# SNI_PROTO_sch.net
KiCad netlist of a schematic drawn in Altium Designer
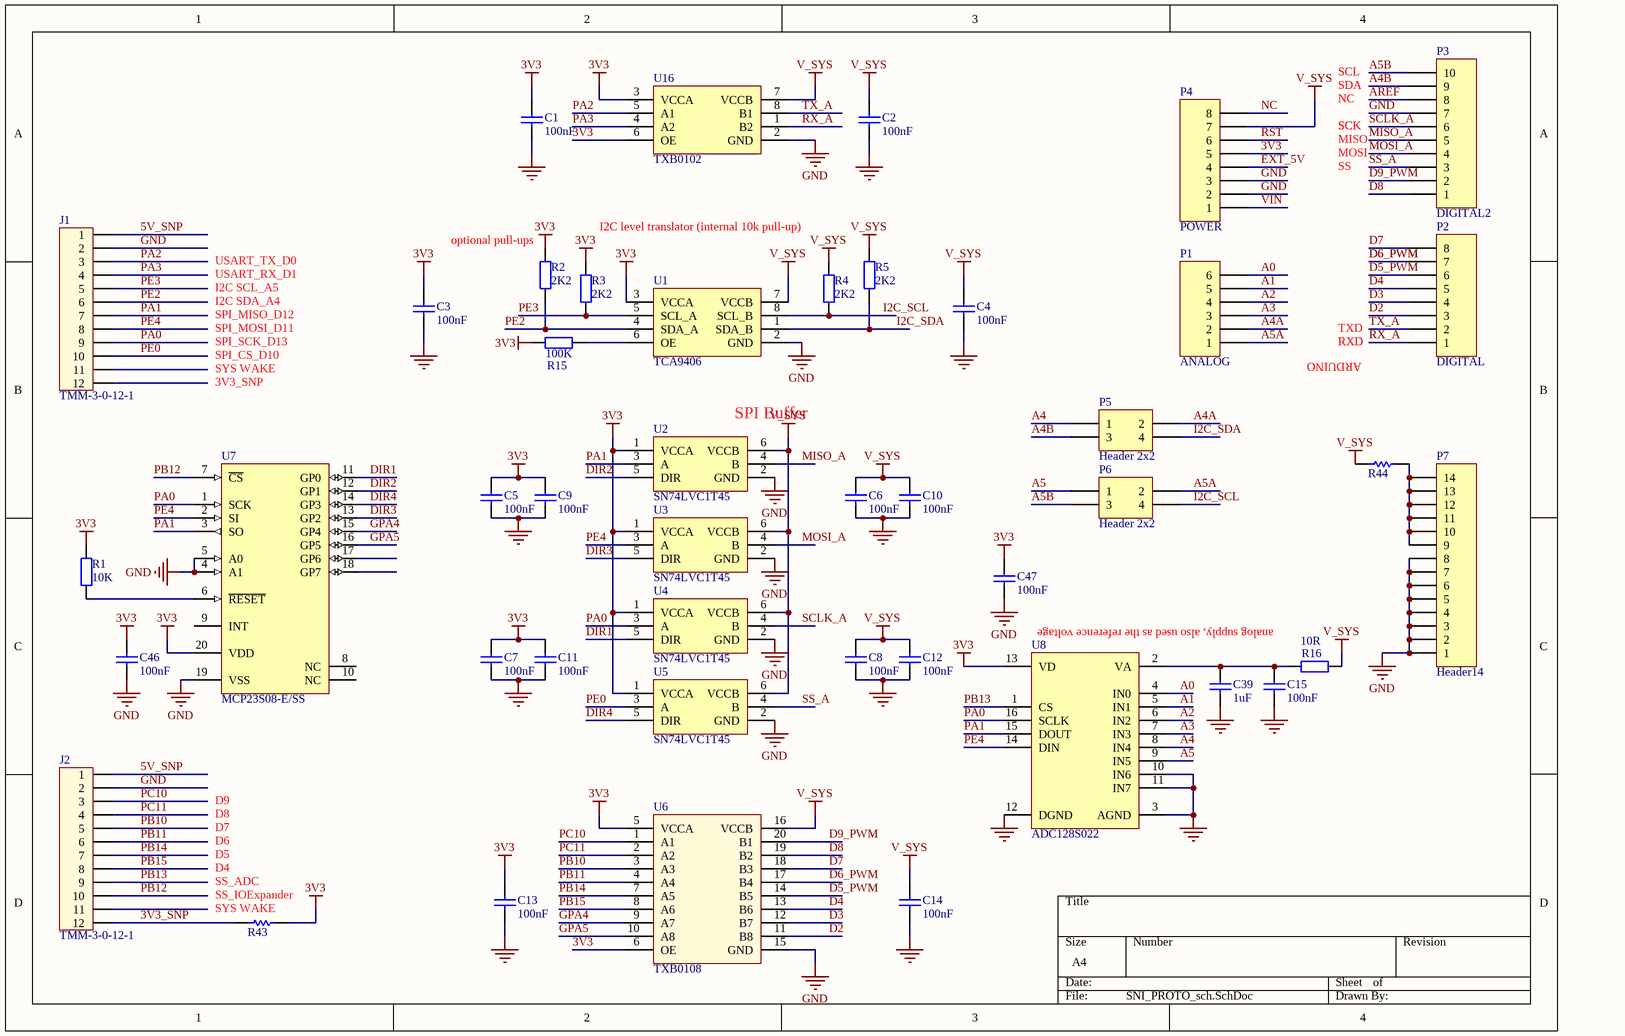
[diagram p0: SNI_PROTO_sch.SchDoc]

(export (version "E")
  (design (tool "Eeschema 10.0.6"))
  (components
    (comp (ref "C1")
      (value "100nF")
      (footprint "CAPC0402(1005)60_L")
      (description "CAP 100nF 10V ±5% 0402 (1005 Metric) Thickness 0.6mm SMD")
      (fields (field (name "TOLERANCE") "Â±5%") (field (name "Comment") "CAP 100nF 10V 0402(1005)"))
      (libsource (lib "Altium Content Vault") (part "CMP-1034-02064-1"))
    )
    (comp (ref "C2")
      (value "100nF")
      (footprint "CAPC0402(1005)60_L")
      (description "CAP 100nF 10V ±5% 0402 (1005 Metric) Thickness 0.6mm SMD")
      (fields (field (name "TOLERANCE") "Â±5%") (field (name "Comment") "CAP 100nF 10V 0402(1005)"))
      (libsource (lib "Altium Content Vault") (part "CMP-1034-02064-1"))
    )
    (comp (ref "C3")
      (value "100nF")
      (footprint "CAPC0402(1005)60_L")
      (description "CAP 100nF 10V ±5% 0402 (1005 Metric) Thickness 0.6mm SMD")
      (fields (field (name "TOLERANCE") "Â±5%") (field (name "Comment") "CAP 100nF 10V 0402(1005)"))
      (libsource (lib "Altium Content Vault") (part "CMP-1034-02064-1"))
    )
    (comp (ref "C4")
      (value "100nF")
      (footprint "CAPC0402(1005)60_L")
      (description "CAP 100nF 10V ±5% 0402 (1005 Metric) Thickness 0.6mm SMD")
      (fields (field (name "TOLERANCE") "Â±5%") (field (name "Comment") "CAP 100nF 10V 0402(1005)"))
      (libsource (lib "Altium Content Vault") (part "CMP-1034-02064-1"))
    )
    (comp (ref "C5")
      (value "100nF")
      (footprint "CAPC0402(1005)60_L")
      (description "CAP 100nF 10V ±5% 0402 (1005 Metric) Thickness 0.6mm SMD")
      (fields (field (name "TOLERANCE") "Â±5%") (field (name "Comment") "CAP 100nF 10V 0402(1005)"))
      (libsource (lib "Altium Content Vault") (part "CMP-1034-02064-1"))
    )
    (comp (ref "C6")
      (value "100nF")
      (footprint "CAPC0402(1005)60_L")
      (description "CAP 100nF 10V ±5% 0402 (1005 Metric) Thickness 0.6mm SMD")
      (fields (field (name "TOLERANCE") "Â±5%") (field (name "Comment") "CAP 100nF 10V 0402(1005)"))
      (libsource (lib "Altium Content Vault") (part "CMP-1034-02064-1"))
    )
    (comp (ref "C7")
      (value "100nF")
      (footprint "CAPC0402(1005)60_L")
      (description "CAP 100nF 10V ±5% 0402 (1005 Metric) Thickness 0.6mm SMD")
      (fields (field (name "TOLERANCE") "Â±5%") (field (name "Comment") "CAP 100nF 10V 0402(1005)"))
      (libsource (lib "Altium Content Vault") (part "CMP-1034-02064-1"))
    )
    (comp (ref "C8")
      (value "100nF")
      (footprint "CAPC0402(1005)60_L")
      (description "CAP 100nF 10V ±5% 0402 (1005 Metric) Thickness 0.6mm SMD")
      (fields (field (name "TOLERANCE") "Â±5%") (field (name "Comment") "CAP 100nF 10V 0402(1005)"))
      (libsource (lib "Altium Content Vault") (part "CMP-1034-02064-1"))
    )
    (comp (ref "C9")
      (value "100nF")
      (footprint "CAPC0402(1005)60_L")
      (description "CAP 100nF 10V ±5% 0402 (1005 Metric) Thickness 0.6mm SMD")
      (fields (field (name "TOLERANCE") "Â±5%") (field (name "Comment") "CAP 100nF 10V 0402(1005)"))
      (libsource (lib "Altium Content Vault") (part "CMP-1034-02064-1"))
    )
    (comp (ref "C10")
      (value "100nF")
      (footprint "CAPC0402(1005)60_L")
      (description "CAP 100nF 10V ±5% 0402 (1005 Metric) Thickness 0.6mm SMD")
      (fields (field (name "TOLERANCE") "Â±5%") (field (name "Comment") "CAP 100nF 10V 0402(1005)"))
      (libsource (lib "Altium Content Vault") (part "CMP-1034-02064-1"))
    )
    (comp (ref "C11")
      (value "100nF")
      (footprint "CAPC0402(1005)60_L")
      (description "CAP 100nF 10V ±5% 0402 (1005 Metric) Thickness 0.6mm SMD")
      (fields (field (name "TOLERANCE") "Â±5%") (field (name "Comment") "CAP 100nF 10V 0402(1005)"))
      (libsource (lib "Altium Content Vault") (part "CMP-1034-02064-1"))
    )
    (comp (ref "C12")
      (value "100nF")
      (footprint "CAPC0402(1005)60_L")
      (description "CAP 100nF 10V ±5% 0402 (1005 Metric) Thickness 0.6mm SMD")
      (fields (field (name "TOLERANCE") "Â±5%") (field (name "Comment") "CAP 100nF 10V 0402(1005)"))
      (libsource (lib "Altium Content Vault") (part "CMP-1034-02064-1"))
    )
    (comp (ref "C13")
      (value "100nF")
      (footprint "CAPC0402(1005)60_L")
      (description "CAP 100nF 10V ±5% 0402 (1005 Metric) Thickness 0.6mm SMD")
      (fields (field (name "TOLERANCE") "Â±5%") (field (name "Comment") "CAP 100nF 10V 0402(1005)"))
      (libsource (lib "Altium Content Vault") (part "CMP-1034-02064-1"))
    )
    (comp (ref "C14")
      (value "100nF")
      (footprint "CAPC0402(1005)60_L")
      (description "CAP 100nF 10V ±5% 0402 (1005 Metric) Thickness 0.6mm SMD")
      (fields (field (name "TOLERANCE") "Â±5%") (field (name "Comment") "CAP 100nF 10V 0402(1005)"))
      (libsource (lib "Altium Content Vault") (part "CMP-1034-02064-1"))
    )
    (comp (ref "C15")
      (value "100nF")
      (footprint "CAPC0402(1005)60_L")
      (description "CAP 100nF 10V ±5% 0402 (1005 Metric) Thickness 0.6mm SMD")
      (fields (field (name "TOLERANCE") "Â±5%") (field (name "Comment") "CAP 100nF 10V 0402(1005)"))
      (libsource (lib "Altium Content Vault") (part "CMP-1034-02064-1"))
    )
    (comp (ref "C39")
      (value "1uF")
      (footprint "CAPC0402(1005)60_L")
      (description "CAP 1uF 10V ±20% 0402 (1005 Metric) Thickness 0.6mm SMD")
      (fields (field (name "TOLERANCE") "Â±20%") (field (name "Comment") "CAP 1uF 10V 0402(1005)"))
      (libsource (lib "Altium Content Vault") (part "CMP-1034-02117-1"))
    )
    (comp (ref "C46")
      (value "100nF")
      (footprint "CAPC0402(1005)60_L")
      (description "CAP 100nF 10V ±5% 0402 (1005 Metric) Thickness 0.6mm SMD")
      (fields (field (name "TOLERANCE") "Â±5%") (field (name "Comment") "CAP 100nF 10V 0402(1005)"))
      (libsource (lib "Altium Content Vault") (part "CMP-1034-02064-1"))
    )
    (comp (ref "C47")
      (value "100nF")
      (footprint "CAPC0402(1005)60_L")
      (description "CAP 100nF 10V ±5% 0402 (1005 Metric) Thickness 0.6mm SMD")
      (fields (field (name "TOLERANCE") "Â±5%") (field (name "Comment") "CAP 100nF 10V 0402(1005)"))
      (libsource (lib "Altium Content Vault") (part "CMP-1034-02064-1"))
    )
    (comp (ref "J1")
      (value "TMM-3-0-12-1")
      (footprint "TMM-3-0-12-1")
      (description "PLUG, DIP, 1.27MM, 12WAY")
      (fields (field (name "MANUFACTURER") "AMPHENOL"))
      (libsource (lib "TMM-3-0-12-1") (part "TMM-3-0-12-1"))
    )
    (comp (ref "J2")
      (value "TMM-3-0-12-1")
      (footprint "TMM-3-0-12-1")
      (description "PLUG, DIP, 1.27MM, 12WAY")
      (fields (field (name "MANUFACTURER") "AMPHENOL"))
      (libsource (lib "TMM-3-0-12-1") (part "TMM-3-0-12-1"))
    )
    (comp (ref "P1") (value "ANALOG") (footprint "H6A") (libsource (lib "Headers_various") (part "header6A")))
    (comp (ref "P2") (value "DIGITAL") (footprint "H8A") (libsource (lib "") (part "Header8A_1")))
    (comp (ref "P3")
      (value "DIGITAL2")
      (footprint "H10A")
      (libsource (lib "Headers_various") (part "Header10A"))
    )
    (comp (ref "P4") (value "POWER") (footprint "H8A") (libsource (lib "Headers_various") (part "Header8A")))
    (comp (ref "P5")
      (value "Header 2x2")
      (footprint "H2x2")
      (libsource (lib "Headers_various") (part "Header"))
    )
    (comp (ref "P6")
      (value "Header 2x2")
      (footprint "H2x2")
      (libsource (lib "Headers_various") (part "Header"))
    )
    (comp (ref "P7")
      (value "Header14")
      (footprint "H14")
      (libsource (lib "Headers_various") (part "Header14"))
    )
    (comp (ref "R1")
      (value "10K")
      (footprint "RESC0402(1005)_L")
      (description "10K 0.063W 1% 0402 (1005 Metric)  SMD")
      (fields (field (name "POWER") "0.063W") (field (name "TOLERANCE") "1%"))
      (libsource (lib "RES0402(1005)") (part "10K 0402(1005)_1"))
    )
    (comp (ref "R2")
      (value "2K2")
      (footprint "RESC0402(1005)_L")
      (description "2K2 0.063W 1% 0402 (1005 Metric)  SMD")
      (fields (field (name "POWER") "0.063W") (field (name "TOLERANCE") "1%"))
      (libsource (lib "RES0402(1005)") (part "2K2 0402(1005)"))
    )
    (comp (ref "R3")
      (value "2K2")
      (footprint "RESC0402(1005)_L")
      (description "2K2 0.063W 1% 0402 (1005 Metric)  SMD")
      (fields (field (name "POWER") "0.063W") (field (name "TOLERANCE") "1%"))
      (libsource (lib "RES0402(1005)") (part "2K2 0402(1005)"))
    )
    (comp (ref "R4")
      (value "2K2")
      (footprint "RESC0402(1005)_L")
      (description "2K2 0.063W 1% 0402 (1005 Metric)  SMD")
      (fields (field (name "POWER") "0.063W") (field (name "TOLERANCE") "1%"))
      (libsource (lib "RES0402(1005)") (part "2K2 0402(1005)"))
    )
    (comp (ref "R5")
      (value "2K2")
      (footprint "RESC0402(1005)_L")
      (description "2K2 0.063W 1% 0402 (1005 Metric)  SMD")
      (fields (field (name "POWER") "0.063W") (field (name "TOLERANCE") "1%"))
      (libsource (lib "RES0402(1005)") (part "2K2 0402(1005)"))
    )
    (comp (ref "R15")
      (value "100K")
      (footprint "RESC0402(1005)_L")
      (description "100K 0.063W 1% 0402 (1005 Metric)  SMD")
      (fields (field (name "POWER") "0.063W") (field (name "TOLERANCE") "1%"))
      (libsource (lib "RES0402(1005)") (part "100K 0402(1005)"))
    )
    (comp (ref "R16")
      (value "10R")
      (footprint "RESC0603(1608)_N")
      (description "10R 0.1W 1% 0603 (1608 Metric)  SMD")
      (fields (field (name "POWER") "0.1W") (field (name "TOLERANCE") "1%"))
      (libsource (lib "RES0603(1608)") (part "10R 0603(1608)"))
    )
    (comp (ref "R43")
      (value "Jumper 0805(2012)")
      (footprint "RESC0805(2012)_N")
      (description "Jumper 0805 (2012 Metric)")
      (fields (field (name "TOLERANCE") "None"))
      (libsource (lib "Altium Content Vault") (part "CMP-1013-00001-1"))
    )
    (comp (ref "R44")
      (value "1R 5% 1210(3225)")
      (footprint "RESC1210(3225)_N")
      (description "1R 0.5W 5% 1210 (3225 Metric)  SMD")
      (fields (field (name "POWER") "0.5 W") (field (name "TOLERANCE") "5 %"))
      (libsource (lib "Altium Content Vault") (part "CMP-1015-00002-1"))
    )
    (comp (ref "U1") (value "TCA9406") (footprint "LSSOP-8") (libsource (lib "TCA9406") (part "TCA9406")))
    (comp (ref "U2")
      (value "SN74LVC1T45")
      (footprint "SOT6_DRL")
      (libsource (lib "SN74LVC1T45") (part "SN74LVC1T45"))
    )
    (comp (ref "U3")
      (value "SN74LVC1T45")
      (footprint "SOT6_DRL")
      (libsource (lib "SN74LVC1T45") (part "SN74LVC1T45"))
    )
    (comp (ref "U4")
      (value "SN74LVC1T45")
      (footprint "SOT6_DRL")
      (libsource (lib "SN74LVC1T45") (part "SN74LVC1T45"))
    )
    (comp (ref "U5")
      (value "SN74LVC1T45")
      (footprint "SOT6_DRL")
      (libsource (lib "SN74LVC1T45") (part "SN74LVC1T45"))
    )
    (comp (ref "U6")
      (value "TXB0108")
      (footprint "UFDFN-20")
      (description "Translator, Bidirectional, 8 bits data rate 100Mbps")
      (fields
        (field (name "MANUFACTURER PART NUMBER") "TXB0108DQSR")
        (field (name "MANUFACTURER") "Texas Instruments")
      )
      (libsource (lib "TXB0108") (part "TXB0108"))
    )
    (comp (ref "U7")
      (value "MCP23S08-E/SS")
      (footprint "SSOP-SS20_N")
      (description "8-Bit I/O Expander with Serial Interface, 20-Pin SSOP, Extended Temperature")
      (fields (field (name "PUBLISHER") "Altium Limited"))
      (libsource (lib "Microchip Interface") (part "MCP23S08-E/SS"))
    )
    (comp (ref "U8")
      (value "ADC128S022")
      (footprint "TSSOP16")
      (libsource (lib "ADC128S022") (part "ADC128S022"))
    )
    (comp (ref "U16") (value "TXB0102") (footprint "VSSOP8") (libsource (lib "TXB0102") (part "TXB0102")))
  )
  (nets
    (net (code "1") (name "/3V3_SNP") (class "Default")
      (node (ref "J2") (pin "12") (pinfunction "12_12") (pintype "passive"))
      (node (ref "R43") (pin "1") (pinfunction "1_1") (pintype "passive"))
    )
    (net (code "2") (name "/5V_SNP") (class "Default")
      (node (ref "J1") (pin "1") (pinfunction "1_1") (pintype "passive"))
      (node (ref "J2") (pin "1") (pinfunction "1_1") (pintype "passive"))
    )
    (net (code "3") (name "/A0") (class "Default")
      (node (ref "P1") (pin "6") (pinfunction "6_6") (pintype "passive"))
      (node (ref "U8") (pin "4") (pinfunction "IN0_4") (pintype "passive"))
    )
    (net (code "4") (name "/A1") (class "Default")
      (node (ref "P1") (pin "5") (pinfunction "5_5") (pintype "passive"))
      (node (ref "U8") (pin "5") (pinfunction "IN1_5") (pintype "passive"))
    )
    (net (code "5") (name "/A2") (class "Default")
      (node (ref "P1") (pin "4") (pinfunction "4_4") (pintype "passive"))
      (node (ref "U8") (pin "6") (pinfunction "IN2_6") (pintype "passive"))
    )
    (net (code "6") (name "/A3") (class "Default")
      (node (ref "P1") (pin "3") (pinfunction "3_3") (pintype "passive"))
      (node (ref "U8") (pin "7") (pinfunction "IN3_7") (pintype "passive"))
    )
    (net (code "7") (name "/A4") (class "Default")
      (node (ref "P5") (pin "1") (pinfunction "1_1") (pintype "passive"))
      (node (ref "U8") (pin "8") (pinfunction "IN4_8") (pintype "passive"))
    )
    (net (code "8") (name "/A4A") (class "Default")
      (node (ref "P1") (pin "2") (pinfunction "2_2") (pintype "passive"))
      (node (ref "P5") (pin "2") (pinfunction "2_2") (pintype "passive"))
    )
    (net (code "9") (name "/A4B") (class "Default")
      (node (ref "P3") (pin "9") (pinfunction "9_9") (pintype "passive"))
      (node (ref "P5") (pin "3") (pinfunction "3_3") (pintype "passive"))
    )
    (net (code "10") (name "/A5") (class "Default")
      (node (ref "P6") (pin "1") (pinfunction "1_1") (pintype "passive"))
      (node (ref "U8") (pin "9") (pinfunction "IN5_9") (pintype "passive"))
    )
    (net (code "11") (name "/A5A") (class "Default")
      (node (ref "P1") (pin "1") (pinfunction "1_1") (pintype "passive"))
      (node (ref "P6") (pin "2") (pinfunction "2_2") (pintype "passive"))
    )
    (net (code "12") (name "/A5B") (class "Default")
      (node (ref "P3") (pin "10") (pinfunction "10_10") (pintype "passive"))
      (node (ref "P6") (pin "3") (pinfunction "3_3") (pintype "passive"))
    )
    (net (code "13") (name "/AREF") (class "Default")
      (node (ref "P3") (pin "8") (pinfunction "8_8") (pintype "passive"))
    )
    (net (code "14") (name "/D2") (class "Default")
      (node (ref "P2") (pin "3") (pinfunction "3_3") (pintype "passive"))
      (node (ref "U6") (pin "11") (pinfunction "B8_11") (pintype "passive"))
    )
    (net (code "15") (name "/D3") (class "Default")
      (node (ref "P2") (pin "4") (pinfunction "4_4") (pintype "passive"))
      (node (ref "U6") (pin "12") (pinfunction "B7_12") (pintype "passive"))
    )
    (net (code "16") (name "/D4") (class "Default")
      (node (ref "P2") (pin "5") (pinfunction "5_5") (pintype "passive"))
      (node (ref "U6") (pin "13") (pinfunction "B6_13") (pintype "passive"))
    )
    (net (code "17") (name "/D5_PWM") (class "Default")
      (node (ref "P2") (pin "6") (pinfunction "6_6") (pintype "passive"))
      (node (ref "U6") (pin "14") (pinfunction "B5_14") (pintype "passive"))
    )
    (net (code "18") (name "/D6_PWM") (class "Default")
      (node (ref "P2") (pin "7") (pinfunction "7_7") (pintype "passive"))
      (node (ref "U6") (pin "17") (pinfunction "B4_17") (pintype "passive"))
    )
    (net (code "19") (name "/D7") (class "Default")
      (node (ref "P2") (pin "8") (pinfunction "8_8") (pintype "passive"))
      (node (ref "U6") (pin "18") (pinfunction "B3_18") (pintype "passive"))
    )
    (net (code "20") (name "/D8") (class "Default")
      (node (ref "P3") (pin "1") (pinfunction "1_1") (pintype "passive"))
      (node (ref "U6") (pin "19") (pinfunction "B2_19") (pintype "passive"))
    )
    (net (code "21") (name "/D9_PWM") (class "Default")
      (node (ref "P3") (pin "2") (pinfunction "2_2") (pintype "passive"))
      (node (ref "U6") (pin "20") (pinfunction "B1_20") (pintype "passive"))
    )
    (net (code "22") (name "/DIR1") (class "Default")
      (node (ref "U4") (pin "5") (pinfunction "DIR_5") (pintype "passive"))
      (node (ref "U7") (pin "11") (pinfunction "GP0_11") (pintype "bidirectional"))
    )
    (net (code "23") (name "/DIR2") (class "Default")
      (node (ref "U2") (pin "5") (pinfunction "DIR_5") (pintype "passive"))
      (node (ref "U7") (pin "12") (pinfunction "GP1_12") (pintype "bidirectional"))
    )
    (net (code "24") (name "/DIR3") (class "Default")
      (node (ref "U3") (pin "5") (pinfunction "DIR_5") (pintype "passive"))
      (node (ref "U7") (pin "13") (pinfunction "GP2_13") (pintype "bidirectional"))
    )
    (net (code "25") (name "/DIR4") (class "Default")
      (node (ref "U5") (pin "5") (pinfunction "DIR_5") (pintype "passive"))
      (node (ref "U7") (pin "14") (pinfunction "GP3_14") (pintype "bidirectional"))
    )
    (net (code "26") (name "/EXT_5V") (class "Default")
      (node (ref "P4") (pin "4") (pinfunction "4_4") (pintype "passive"))
    )
    (net (code "27") (name "/GPA4") (class "Default")
      (node (ref "U6") (pin "9") (pinfunction "A7_9") (pintype "passive"))
      (node (ref "U7") (pin "15") (pinfunction "GP4_15") (pintype "bidirectional"))
    )
    (net (code "28") (name "/GPA5") (class "Default")
      (node (ref "U6") (pin "10") (pinfunction "A8_10") (pintype "passive"))
      (node (ref "U7") (pin "16") (pinfunction "GP5_16") (pintype "bidirectional"))
    )
    (net (code "29") (name "/I2C_SCL") (class "Default")
      (node (ref "P6") (pin "4") (pinfunction "4_4") (pintype "passive"))
      (node (ref "R4") (pin "1") (pinfunction "1_1") (pintype "passive"))
      (node (ref "U1") (pin "8") (pinfunction "SCL_B_8") (pintype "passive"))
    )
    (net (code "30") (name "/I2C_SDA") (class "Default")
      (node (ref "P5") (pin "4") (pinfunction "4_4") (pintype "passive"))
      (node (ref "R5") (pin "1") (pinfunction "1_1") (pintype "passive"))
      (node (ref "U1") (pin "1") (pinfunction "SDA_B_1") (pintype "passive"))
    )
    (net (code "31") (name "/MISO_A") (class "Default")
      (node (ref "P3") (pin "5") (pinfunction "5_5") (pintype "passive"))
      (node (ref "U2") (pin "4") (pinfunction "B_4") (pintype "passive"))
    )
    (net (code "32") (name "/MOSI_A") (class "Default")
      (node (ref "P3") (pin "4") (pinfunction "4_4") (pintype "passive"))
      (node (ref "U3") (pin "4") (pinfunction "B_4") (pintype "passive"))
    )
    (net (code "33") (name "/NC") (class "Default")
      (node (ref "P4") (pin "8") (pinfunction "8_8") (pintype "passive"))
    )
    (net (code "34") (name "/PA0") (class "Default")
      (node (ref "J1") (pin "9") (pinfunction "9_9") (pintype "passive"))
      (node (ref "U4") (pin "3") (pinfunction "A_3") (pintype "passive"))
      (node (ref "U7") (pin "1") (pinfunction "SCK_1") (pintype "input"))
      (node (ref "U8") (pin "16") (pinfunction "SCLK_16") (pintype "passive"))
    )
    (net (code "35") (name "/PA1") (class "Default")
      (node (ref "J1") (pin "7") (pinfunction "7_7") (pintype "passive"))
      (node (ref "U2") (pin "3") (pinfunction "A_3") (pintype "passive"))
      (node (ref "U7") (pin "3") (pinfunction "SO_3") (pintype "output"))
      (node (ref "U8") (pin "15") (pinfunction "DOUT_15") (pintype "passive"))
    )
    (net (code "36") (name "/PA2") (class "Default")
      (node (ref "J1") (pin "3") (pinfunction "3_3") (pintype "passive"))
      (node (ref "U16") (pin "5") (pinfunction "A1_5") (pintype "passive"))
    )
    (net (code "37") (name "/PA3") (class "Default")
      (node (ref "J1") (pin "4") (pinfunction "4_4") (pintype "passive"))
      (node (ref "U16") (pin "4") (pinfunction "A2_4") (pintype "passive"))
    )
    (net (code "38") (name "/PB10") (class "Default")
      (node (ref "J2") (pin "5") (pinfunction "5_5") (pintype "passive"))
      (node (ref "U6") (pin "3") (pinfunction "A3_3") (pintype "passive"))
    )
    (net (code "39") (name "/PB11") (class "Default")
      (node (ref "J2") (pin "6") (pinfunction "6_6") (pintype "passive"))
      (node (ref "U6") (pin "4") (pinfunction "A4_4") (pintype "passive"))
    )
    (net (code "40") (name "/PB12") (class "Default")
      (node (ref "J2") (pin "10") (pinfunction "10_10") (pintype "passive"))
      (node (ref "U7") (pin "7") (pinfunction "~{CS}_7") (pintype "input"))
    )
    (net (code "41") (name "/PB13") (class "Default")
      (node (ref "J2") (pin "9") (pinfunction "9_9") (pintype "passive"))
      (node (ref "U8") (pin "1") (pinfunction "CS_1") (pintype "passive"))
    )
    (net (code "42") (name "/PB14") (class "Default")
      (node (ref "J2") (pin "7") (pinfunction "7_7") (pintype "passive"))
      (node (ref "U6") (pin "7") (pinfunction "A5_7") (pintype "passive"))
    )
    (net (code "43") (name "/PB15") (class "Default")
      (node (ref "J2") (pin "8") (pinfunction "8_8") (pintype "passive"))
      (node (ref "U6") (pin "8") (pinfunction "A6_8") (pintype "passive"))
    )
    (net (code "44") (name "/PC10") (class "Default")
      (node (ref "J2") (pin "3") (pinfunction "3_3") (pintype "passive"))
      (node (ref "U6") (pin "1") (pinfunction "A1_1") (pintype "passive"))
    )
    (net (code "45") (name "/PC11") (class "Default")
      (node (ref "J2") (pin "4") (pinfunction "4_4") (pintype "passive"))
      (node (ref "U6") (pin "2") (pinfunction "A2_2") (pintype "passive"))
    )
    (net (code "46") (name "/PE0") (class "Default")
      (node (ref "J1") (pin "10") (pinfunction "10_10") (pintype "passive"))
      (node (ref "U5") (pin "3") (pinfunction "A_3") (pintype "passive"))
    )
    (net (code "47") (name "/PE2") (class "Default")
      (node (ref "J1") (pin "6") (pinfunction "6_6") (pintype "passive"))
      (node (ref "R2") (pin "1") (pinfunction "1_1") (pintype "passive"))
      (node (ref "U1") (pin "4") (pinfunction "SDA_A_4") (pintype "passive"))
    )
    (net (code "48") (name "/PE3") (class "Default")
      (node (ref "J1") (pin "5") (pinfunction "5_5") (pintype "passive"))
      (node (ref "R3") (pin "1") (pinfunction "1_1") (pintype "passive"))
      (node (ref "U1") (pin "5") (pinfunction "SCL_A_5") (pintype "passive"))
    )
    (net (code "49") (name "/PE4") (class "Default")
      (node (ref "J1") (pin "8") (pinfunction "8_8") (pintype "passive"))
      (node (ref "U3") (pin "3") (pinfunction "A_3") (pintype "passive"))
      (node (ref "U7") (pin "2") (pinfunction "SI_2") (pintype "input"))
      (node (ref "U8") (pin "14") (pinfunction "DIN_14") (pintype "passive"))
    )
    (net (code "50") (name "/RST") (class "Default")
      (node (ref "P4") (pin "6") (pinfunction "6_6") (pintype "passive"))
    )
    (net (code "51") (name "/RX_A") (class "Default")
      (node (ref "P2") (pin "1") (pinfunction "1_1") (pintype "passive"))
      (node (ref "U16") (pin "1") (pinfunction "B2_1") (pintype "passive"))
    )
    (net (code "52") (name "/SCLK_A") (class "Default")
      (node (ref "P3") (pin "6") (pinfunction "6_6") (pintype "passive"))
      (node (ref "U4") (pin "4") (pinfunction "B_4") (pintype "passive"))
    )
    (net (code "53") (name "/SS_A") (class "Default")
      (node (ref "P3") (pin "3") (pinfunction "3_3") (pintype "passive"))
      (node (ref "U5") (pin "4") (pinfunction "B_4") (pintype "passive"))
    )
    (net (code "54") (name "/TX_A") (class "Default")
      (node (ref "P2") (pin "2") (pinfunction "2_2") (pintype "passive"))
      (node (ref "U16") (pin "8") (pinfunction "B1_8") (pintype "passive"))
    )
    (net (code "55") (name "/VIN") (class "Default")
      (node (ref "P4") (pin "1") (pinfunction "1_1") (pintype "passive"))
    )
    (net (code "56") (name "3V3") (class "Default")
      (node (ref "C1") (pin "1") (pinfunction "1_1") (pintype "passive"))
      (node (ref "C11") (pin "2") (pinfunction "2_2") (pintype "passive"))
      (node (ref "C13") (pin "2") (pinfunction "2_2") (pintype "passive"))
      (node (ref "C3") (pin "1") (pinfunction "1_1") (pintype "passive"))
      (node (ref "C46") (pin "1") (pinfunction "1_1") (pintype "passive"))
      (node (ref "C47") (pin "1") (pinfunction "1_1") (pintype "passive"))
      (node (ref "C5") (pin "1") (pinfunction "1_1") (pintype "passive"))
      (node (ref "C7") (pin "1") (pinfunction "1_1") (pintype "passive"))
      (node (ref "C9") (pin "2") (pinfunction "2_2") (pintype "passive"))
      (node (ref "P4") (pin "5") (pinfunction "5_5") (pintype "passive"))
      (node (ref "R1") (pin "2") (pinfunction "2_2") (pintype "passive"))
      (node (ref "R15") (pin "1") (pinfunction "1_1") (pintype "passive"))
      (node (ref "R2") (pin "2") (pinfunction "2_2") (pintype "passive"))
      (node (ref "R3") (pin "2") (pinfunction "2_2") (pintype "passive"))
      (node (ref "R43") (pin "2") (pinfunction "2_2") (pintype "passive"))
      (node (ref "U1") (pin "3") (pinfunction "VCCA_3") (pintype "passive"))
      (node (ref "U16") (pin "3") (pinfunction "VCCA_3") (pintype "passive"))
      (node (ref "U16") (pin "6") (pinfunction "OE_6") (pintype "passive"))
      (node (ref "U2") (pin "1") (pinfunction "VCCA_1") (pintype "passive"))
      (node (ref "U3") (pin "1") (pinfunction "VCCA_1") (pintype "passive"))
      (node (ref "U4") (pin "1") (pinfunction "VCCA_1") (pintype "passive"))
      (node (ref "U5") (pin "1") (pinfunction "VCCA_1") (pintype "passive"))
      (node (ref "U6") (pin "5") (pinfunction "VCCA_5") (pintype "passive"))
      (node (ref "U6") (pin "6") (pinfunction "OE_6") (pintype "passive"))
      (node (ref "U7") (pin "20") (pinfunction "VDD_20") (pintype "power_in"))
      (node (ref "U8") (pin "13") (pinfunction "VD_13") (pintype "passive"))
    )
    (net (code "57") (name "GND") (class "Default")
      (node (ref "C1") (pin "2") (pinfunction "2_2") (pintype "passive"))
      (node (ref "C10") (pin "1") (pinfunction "1_1") (pintype "passive"))
      (node (ref "C11") (pin "1") (pinfunction "1_1") (pintype "passive"))
      (node (ref "C12") (pin "1") (pinfunction "1_1") (pintype "passive"))
      (node (ref "C13") (pin "1") (pinfunction "1_1") (pintype "passive"))
      (node (ref "C14") (pin "1") (pinfunction "1_1") (pintype "passive"))
      (node (ref "C15") (pin "1") (pinfunction "1_1") (pintype "passive"))
      (node (ref "C2") (pin "2") (pinfunction "2_2") (pintype "passive"))
      (node (ref "C3") (pin "2") (pinfunction "2_2") (pintype "passive"))
      (node (ref "C39") (pin "1") (pinfunction "1_1") (pintype "passive"))
      (node (ref "C4") (pin "2") (pinfunction "2_2") (pintype "passive"))
      (node (ref "C46") (pin "2") (pinfunction "2_2") (pintype "passive"))
      (node (ref "C47") (pin "2") (pinfunction "2_2") (pintype "passive"))
      (node (ref "C5") (pin "2") (pinfunction "2_2") (pintype "passive"))
      (node (ref "C6") (pin "2") (pinfunction "2_2") (pintype "passive"))
      (node (ref "C7") (pin "2") (pinfunction "2_2") (pintype "passive"))
      (node (ref "C8") (pin "2") (pinfunction "2_2") (pintype "passive"))
      (node (ref "C9") (pin "1") (pinfunction "1_1") (pintype "passive"))
      (node (ref "J1") (pin "2") (pinfunction "2_2") (pintype "passive"))
      (node (ref "J2") (pin "2") (pinfunction "2_2") (pintype "passive"))
      (node (ref "P3") (pin "7") (pinfunction "7_7") (pintype "passive"))
      (node (ref "P4") (pin "2") (pinfunction "2_2") (pintype "passive"))
      (node (ref "P4") (pin "3") (pinfunction "3_3") (pintype "passive"))
      (node (ref "P7") (pin "1") (pinfunction "1_1") (pintype "passive"))
      (node (ref "P7") (pin "2") (pinfunction "2_2") (pintype "passive"))
      (node (ref "P7") (pin "3") (pinfunction "3_3") (pintype "passive"))
      (node (ref "P7") (pin "4") (pinfunction "4_4") (pintype "passive"))
      (node (ref "P7") (pin "5") (pinfunction "5_5") (pintype "passive"))
      (node (ref "P7") (pin "6") (pinfunction "6_6") (pintype "passive"))
      (node (ref "P7") (pin "7") (pinfunction "7_7") (pintype "passive"))
      (node (ref "P7") (pin "8") (pinfunction "8_8") (pintype "passive"))
      (node (ref "U1") (pin "2") (pinfunction "GND_2") (pintype "passive"))
      (node (ref "U16") (pin "2") (pinfunction "GND_2") (pintype "passive"))
      (node (ref "U2") (pin "2") (pinfunction "GND_2") (pintype "passive"))
      (node (ref "U3") (pin "2") (pinfunction "GND_2") (pintype "passive"))
      (node (ref "U4") (pin "2") (pinfunction "GND_2") (pintype "passive"))
      (node (ref "U5") (pin "2") (pinfunction "GND_2") (pintype "passive"))
      (node (ref "U6") (pin "15") (pinfunction "GND_15") (pintype "passive"))
      (node (ref "U7") (pin "19") (pinfunction "VSS_19") (pintype "power_in"))
      (node (ref "U7") (pin "4") (pinfunction "A1_4") (pintype "input"))
      (node (ref "U7") (pin "5") (pinfunction "A0_5") (pintype "input"))
      (node (ref "U8") (pin "10") (pinfunction "IN6_10") (pintype "passive"))
      (node (ref "U8") (pin "11") (pinfunction "IN7_11") (pintype "passive"))
      (node (ref "U8") (pin "12") (pinfunction "DGND_12") (pintype "passive"))
      (node (ref "U8") (pin "3") (pinfunction "AGND_3") (pintype "passive"))
    )
    (net (code "58") (name "Net-(P7-Pad10)") (class "Default")
      (node (ref "P7") (pin "10") (pinfunction "10_10") (pintype "passive"))
      (node (ref "P7") (pin "11") (pinfunction "11_11") (pintype "passive"))
      (node (ref "P7") (pin "12") (pinfunction "12_12") (pintype "passive"))
      (node (ref "P7") (pin "13") (pinfunction "13_13") (pintype "passive"))
      (node (ref "P7") (pin "14") (pinfunction "14_14") (pintype "passive"))
      (node (ref "P7") (pin "9") (pinfunction "9_9") (pintype "passive"))
      (node (ref "R44") (pin "2") (pinfunction "2_2") (pintype "passive"))
    )
    (net (code "59") (name "Net-(U1-OE)") (class "Default")
      (node (ref "R15") (pin "2") (pinfunction "2_2") (pintype "passive"))
      (node (ref "U1") (pin "6") (pinfunction "OE_6") (pintype "passive"))
    )
    (net (code "60") (name "Net-(U7-~{RESET})") (class "Default")
      (node (ref "R1") (pin "1") (pinfunction "1_1") (pintype "passive"))
      (node (ref "U7") (pin "6") (pinfunction "~{RESET}_6") (pintype "input"))
    )
    (net (code "61") (name "Net-(U8-VA)") (class "Default")
      (node (ref "C15") (pin "2") (pinfunction "2_2") (pintype "passive"))
      (node (ref "C39") (pin "2") (pinfunction "2_2") (pintype "passive"))
      (node (ref "R16") (pin "1") (pinfunction "1_1") (pintype "passive"))
      (node (ref "U8") (pin "2") (pinfunction "VA_2") (pintype "passive"))
    )
    (net (code "62") (name "V_SYS") (class "Default")
      (node (ref "C10") (pin "2") (pinfunction "2_2") (pintype "passive"))
      (node (ref "C12") (pin "2") (pinfunction "2_2") (pintype "passive"))
      (node (ref "C14") (pin "2") (pinfunction "2_2") (pintype "passive"))
      (node (ref "C2") (pin "1") (pinfunction "1_1") (pintype "passive"))
      (node (ref "C4") (pin "1") (pinfunction "1_1") (pintype "passive"))
      (node (ref "C6") (pin "1") (pinfunction "1_1") (pintype "passive"))
      (node (ref "C8") (pin "1") (pinfunction "1_1") (pintype "passive"))
      (node (ref "P4") (pin "7") (pinfunction "7_7") (pintype "passive"))
      (node (ref "R16") (pin "2") (pinfunction "2_2") (pintype "passive"))
      (node (ref "R4") (pin "2") (pinfunction "2_2") (pintype "passive"))
      (node (ref "R44") (pin "1") (pinfunction "1_1") (pintype "passive"))
      (node (ref "R5") (pin "2") (pinfunction "2_2") (pintype "passive"))
      (node (ref "U1") (pin "7") (pinfunction "VCCB_7") (pintype "passive"))
      (node (ref "U16") (pin "7") (pinfunction "VCCB_7") (pintype "passive"))
      (node (ref "U2") (pin "6") (pinfunction "VCCB_6") (pintype "passive"))
      (node (ref "U3") (pin "6") (pinfunction "VCCB_6") (pintype "passive"))
      (node (ref "U4") (pin "6") (pinfunction "VCCB_6") (pintype "passive"))
      (node (ref "U5") (pin "6") (pinfunction "VCCB_6") (pintype "passive"))
      (node (ref "U6") (pin "16") (pinfunction "VCCB_16") (pintype "passive"))
    )
    (net (code "63") (name "unconnected-(J1-Pad11)") (class "Default")
      (node (ref "J1") (pin "11") (pinfunction "11_11") (pintype "passive"))
    )
    (net (code "64") (name "unconnected-(J1-Pad12)") (class "Default")
      (node (ref "J1") (pin "12") (pinfunction "12_12") (pintype "passive"))
    )
    (net (code "65") (name "unconnected-(J2-Pad11)") (class "Default")
      (node (ref "J2") (pin "11") (pinfunction "11_11") (pintype "passive"))
    )
    (net (code "66") (name "unconnected-(U7-GP6-Pad17)") (class "Default")
      (node (ref "U7") (pin "17") (pinfunction "GP6_17") (pintype "bidirectional"))
    )
    (net (code "67") (name "unconnected-(U7-GP7-Pad18)") (class "Default")
      (node (ref "U7") (pin "18") (pinfunction "GP7_18") (pintype "bidirectional"))
    )
    (net (code "68") (name "unconnected-(U7-INT-Pad9)") (class "Default")
      (node (ref "U7") (pin "9") (pinfunction "INT_9") (pintype "open_collector"))
    )
    (net (code "69") (name "unconnected-(U7-NC-Pad8)") (class "Default")
      (node (ref "U7") (pin "8") (pinfunction "NC_8") (pintype "passive"))
    )
    (net (code "70") (name "unconnected-(U7-NC-Pad10)") (class "Default")
      (node (ref "U7") (pin "10") (pinfunction "NC_10") (pintype "passive"))
    )
  )
)
